# design.net
KiCad netlist of a schematic drawn in EasyEDA Pro
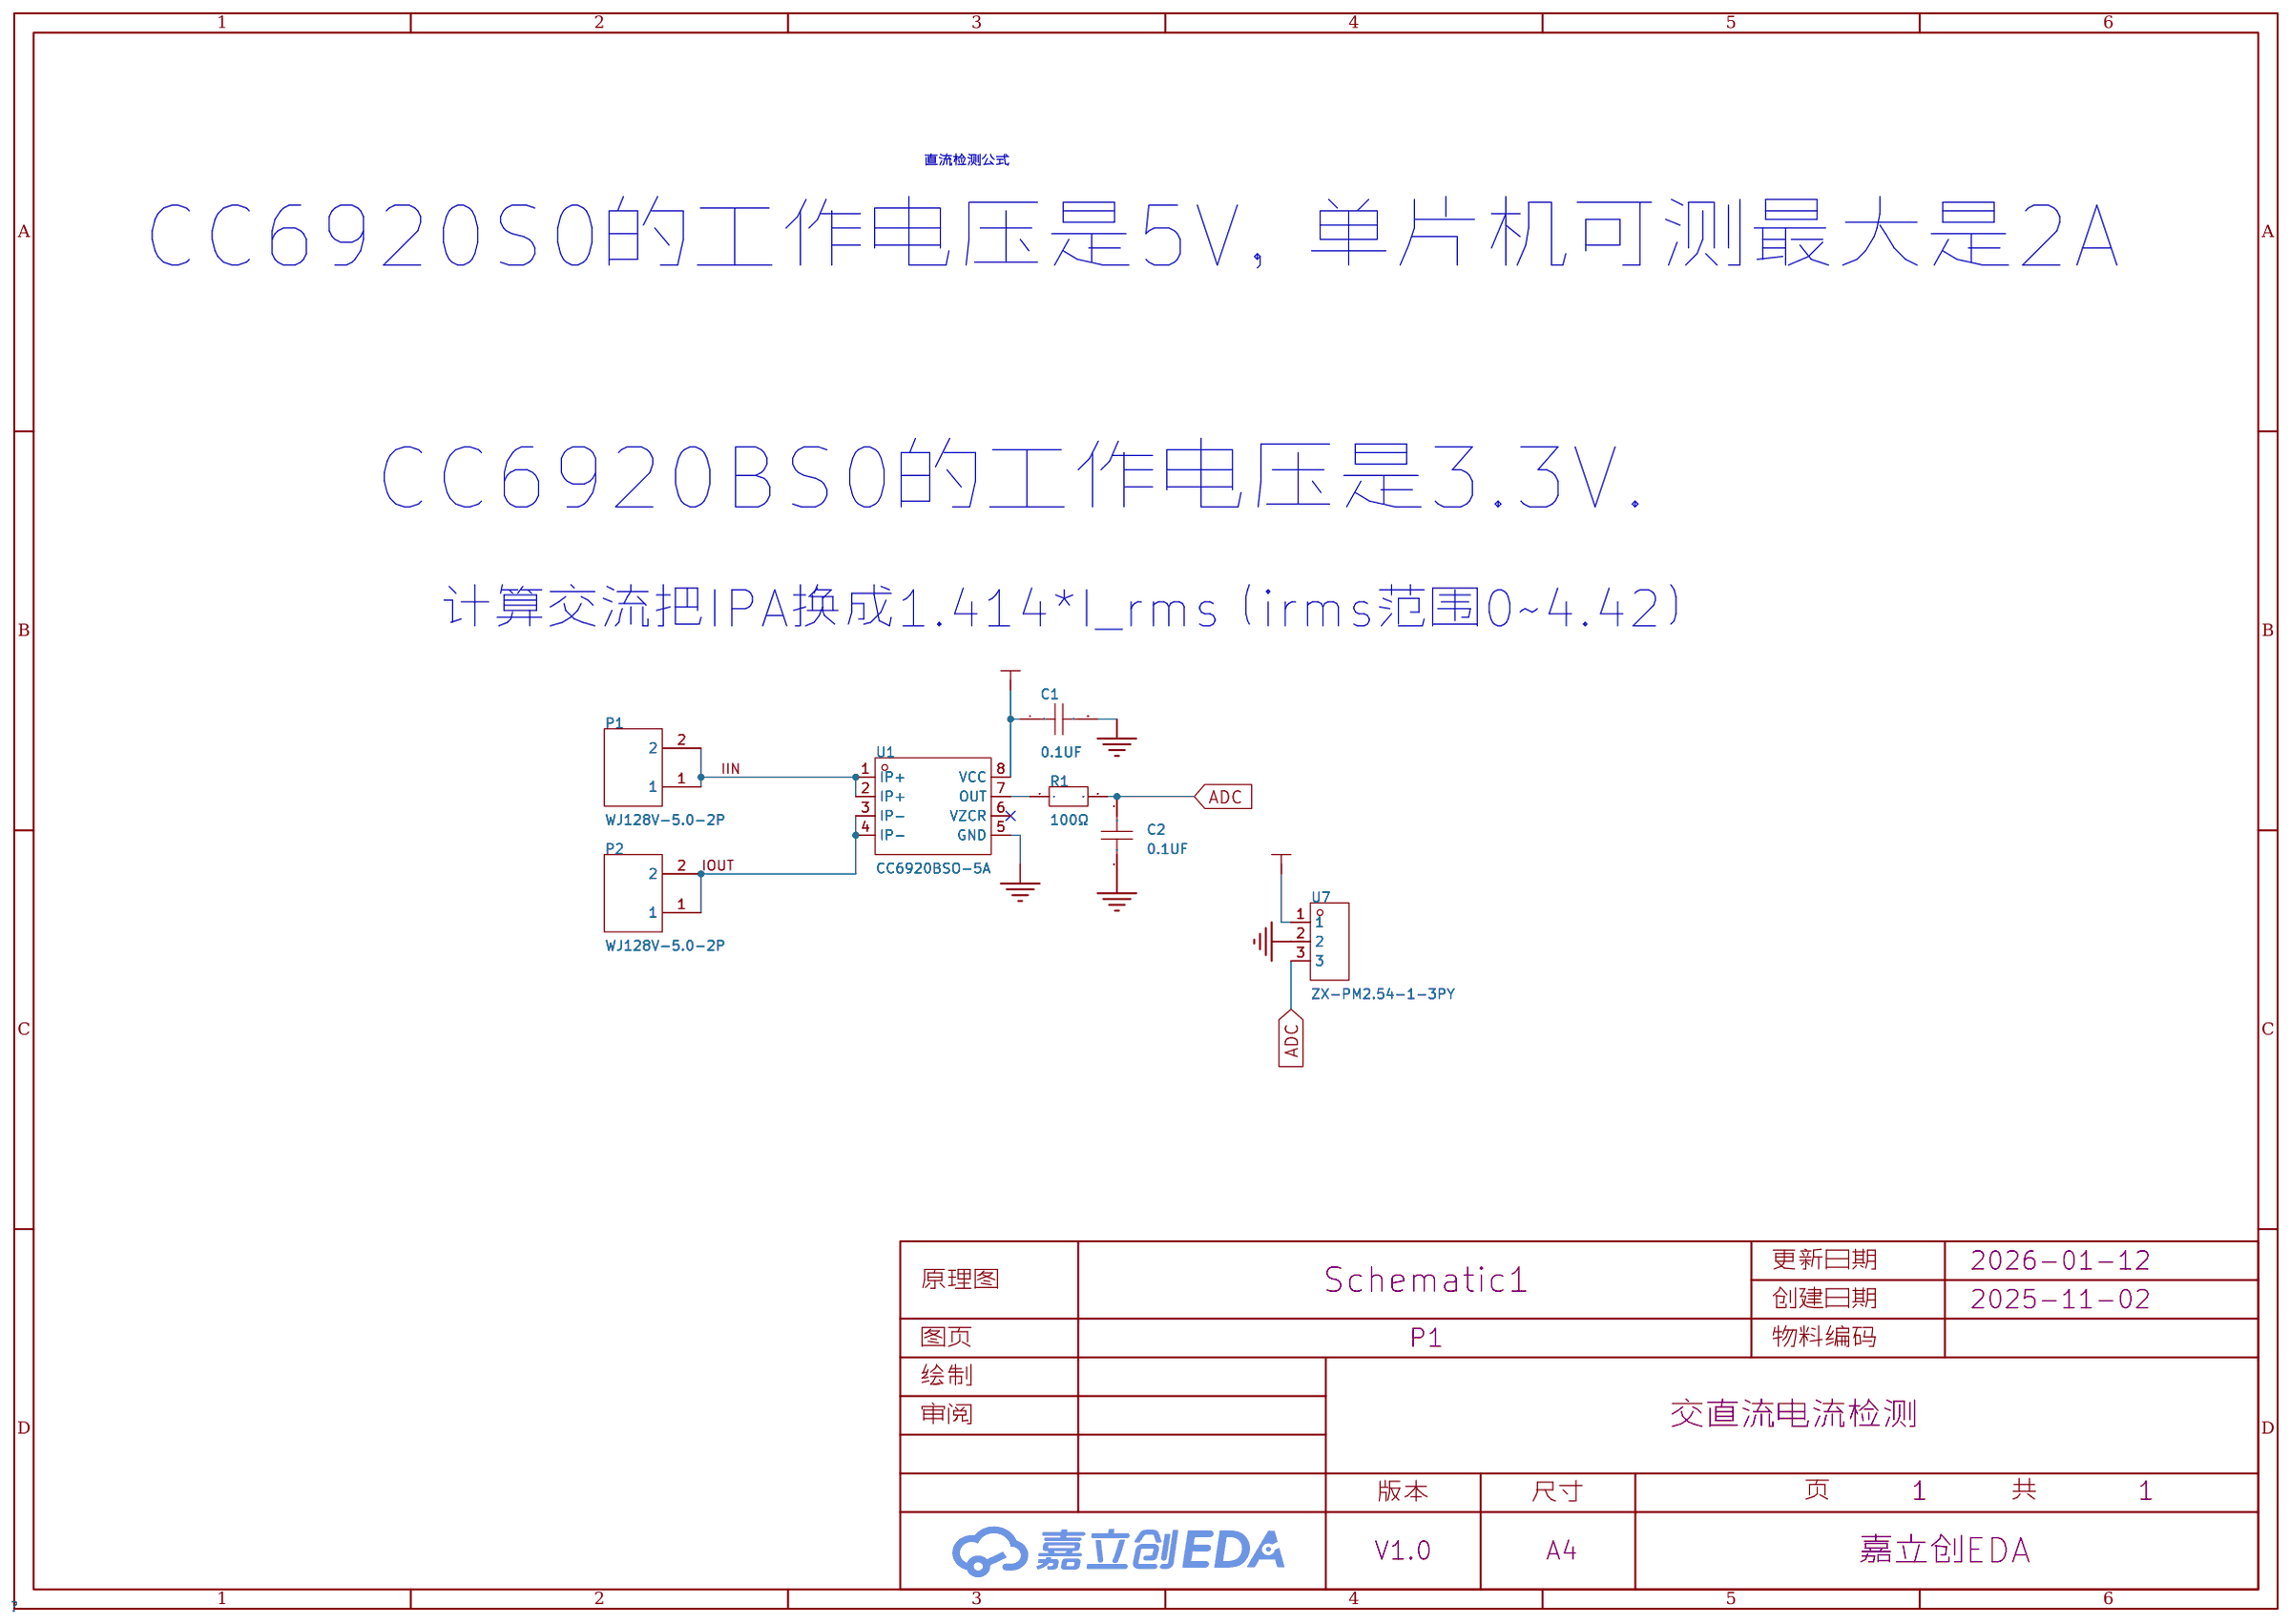
[diagram p0: schematic sheet]

(export (version "E")
  (design (tool "Eeschema 10.0.6"))
  (components
    (comp (ref "C1")
      (value "0.1UF")
      (footprint "easyedapro:C0805")
      (description "容值:10nF;精度:±5%;额定电压:100V;")
      (fields (field (name "Manufacturer Part") "C2012C0G2A103JT000N") (field (name "Manufacturer") "TDK"))
      (libsource (lib "easyedapro") (part "C2012C0G2A103JT000N"))
    )
    (comp (ref "C2")
      (value "0.1UF")
      (footprint "easyedapro:C0805")
      (description "容值:10nF;精度:±5%;额定电压:100V;")
      (fields (field (name "Manufacturer Part") "C2012C0G2A103JT000N") (field (name "Manufacturer") "TDK"))
      (libsource (lib "easyedapro") (part "C2012C0G2A103JT000N"))
    )
    (comp (ref "P1")
      (value "WJ128V-5.0-2P")
      (footprint "easyedapro:CONN-TH_2P-P5.00_WJ128V-5.0-2P")
      (fields (field (name "Manufacturer") "KANGNEX(康奈克斯电气)"))
      (libsource (lib "easyedapro") (part "WJ128V-5.0-2P"))
    )
    (comp (ref "P2")
      (value "WJ128V-5.0-2P")
      (footprint "easyedapro:CONN-TH_2P-P5.00_WJ128V-5.0-2P")
      (fields (field (name "Manufacturer") "KANGNEX(康奈克斯电气)"))
      (libsource (lib "easyedapro") (part "WJ128V-5.0-2P"))
    )
    (comp (ref "R1")
      (value "100Ω")
      (footprint "easyedapro:C0805")
      (description "电阻类型:厚膜电阻;阻值:2.2Ω;精度:±1%;功率:125mW;温度系数:-100ppm/°C~+600ppm/°C;")
      (fields
        (field (name "Manufacturer Part") "ERJ-U06F2R20V")
        (field (name "Manufacturer") "PANASONIC(松下)")
      )
      (libsource (lib "easyedapro") (part "ERJ-U06F2R20V"))
    )
    (comp (ref "U1")
      (value "CC6920BSO-5A")
      (footprint "easyedapro:SOP-8_L4.9-W3.9-P1.27-LS6.0-BL")
      (description "电流测量范围:-5A~5A;隔离耐压:3500Vrms;灵敏度:264mV/A;")
      (fields (field (name "Manufacturer") "CrossChip(成都芯进)"))
      (libsource (lib "easyedapro") (part "CC6920BSO-5A"))
    )
    (comp (ref "U7")
      (value "ZX-PM2.54-1-3PY")
      (footprint "easyedapro:HDR-TH_3P-P2.54-V-F")
      (fields (field (name "Manufacturer") "Megastar(兆星)"))
      (libsource (lib "easyedapro") (part "ZX-PM2.54-1-3PY"))
    )
  )
  (nets
    (net (code "1") (name "+3.3V") (class "Default")
      (node (ref "C1") (pin "1") (pinfunction "1_1") (pintype "unspecified"))
      (node (ref "U1") (pin "8") (pinfunction "VCC_8") (pintype "unspecified"))
      (node (ref "U7") (pin "1") (pinfunction "1_1") (pintype "unspecified"))
    )
    (net (code "2") (name "/IIN") (class "Default")
      (node (ref "P1") (pin "1") (pinfunction "1_1") (pintype "unspecified"))
      (node (ref "P1") (pin "2") (pinfunction "2_2") (pintype "unspecified"))
      (node (ref "U1") (pin "1") (pinfunction "IP+_1") (pintype "unspecified"))
      (node (ref "U1") (pin "2") (pinfunction "IP+_2") (pintype "unspecified"))
    )
    (net (code "3") (name "/IOUT") (class "Default")
      (node (ref "P2") (pin "1") (pinfunction "1_1") (pintype "unspecified"))
      (node (ref "P2") (pin "2") (pinfunction "2_2") (pintype "unspecified"))
      (node (ref "U1") (pin "3") (pinfunction "IP-_3") (pintype "unspecified"))
      (node (ref "U1") (pin "4") (pinfunction "IP-_4") (pintype "unspecified"))
    )
    (net (code "4") (name "ADC") (class "Default")
      (node (ref "C2") (pin "2") (pinfunction "2_2") (pintype "unspecified"))
      (node (ref "R1") (pin "2") (pinfunction "2_2") (pintype "unspecified"))
      (node (ref "U7") (pin "3") (pinfunction "3_3") (pintype "unspecified"))
    )
    (net (code "5") (name "GND") (class "Default")
      (node (ref "C1") (pin "2") (pinfunction "2_2") (pintype "unspecified"))
      (node (ref "C2") (pin "1") (pinfunction "1_1") (pintype "unspecified"))
      (node (ref "U1") (pin "5") (pinfunction "GND_5") (pintype "unspecified"))
      (node (ref "U7") (pin "2") (pinfunction "2_2") (pintype "unspecified"))
    )
    (net (code "6") (name "Net-(U1-OUT)") (class "Default")
      (node (ref "R1") (pin "1") (pinfunction "1_1") (pintype "unspecified"))
      (node (ref "U1") (pin "7") (pinfunction "OUT_7") (pintype "unspecified"))
    )
    (net (code "7") (name "unconnected-(U1-VZCR-Pad6)") (class "Default")
      (node (ref "U1") (pin "6") (pinfunction "VZCR_6") (pintype "unspecified+no_connect"))
    )
  )
)
